# ac_switching.net
KiCad netlist of a schematic drawn in EAGLE
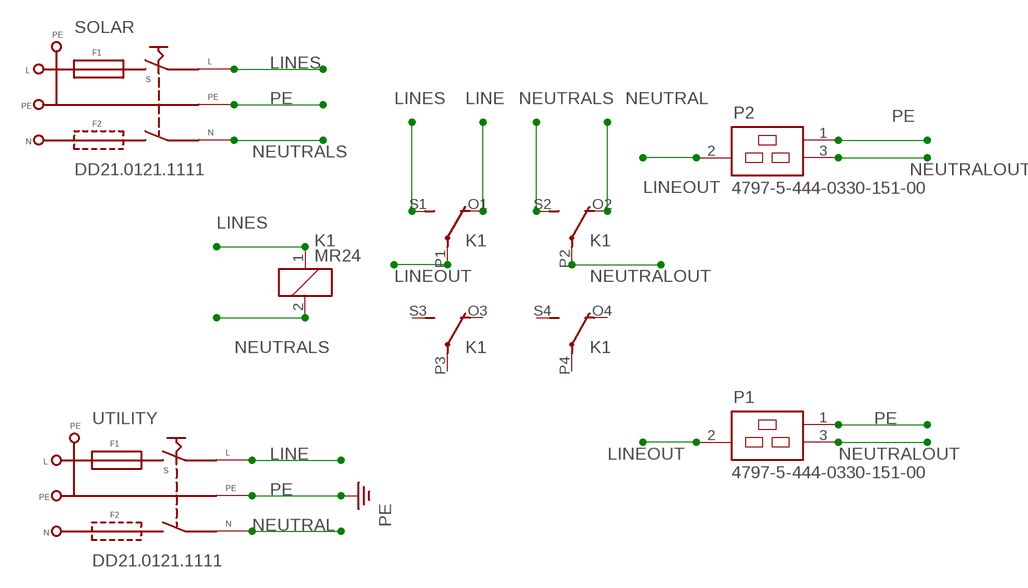
[diagram p0: schematic, sheet 1]

(export (version "E")
  (design (tool "Eeschema 10.0.6"))
  (components
    (comp (ref "K1")
      (value "MR24")
      (footprint "eagle-import:MR24")
      (libsource (lib "eagle-import") (part "MR24"))
    )
    (comp (ref "P1")
      (value "4797-5-444-0330-151-00")
      (footprint "eagle-import:SCHURTER_4797-5-444-0330-151-00")
      (fields (field (name "MF") "Schurter Inc."))
      (libsource (lib "eagle-import") (part "4797-5-444-0330-151-00"))
    )
    (comp (ref "P2")
      (value "4797-5-444-0330-151-00")
      (footprint "eagle-import:SCHURTER_4797-5-444-0330-151-00")
      (fields (field (name "MF") "Schurter Inc."))
      (libsource (lib "eagle-import") (part "4797-5-444-0330-151-00"))
    )
    (comp (ref "SOLAR")
      (value "DD21.0121.1111")
      (footprint "eagle-import:SCHURTER_DD21.0121.1111")
      (fields (field (name "MF") "Schurter Inc."))
      (libsource (lib "eagle-import") (part "DD21.0121.1111"))
    )
    (comp (ref "UTILITY")
      (value "DD21.0121.1111")
      (footprint "eagle-import:SCHURTER_DD21.0121.1111")
      (fields (field (name "MF") "Schurter Inc."))
      (libsource (lib "eagle-import") (part "DD21.0121.1111"))
    )
  )
  (nets
    (net (code "1") (name "/LINE") (class "Default")
      (node (ref "K1") (pin "O1") (pinfunction "O_O1") (pintype "passive"))
      (node (ref "UTILITY") (pin "L") (pinfunction "L_L") (pintype "power_in"))
    )
    (net (code "2") (name "/LINEOUT") (class "Default")
      (node (ref "K1") (pin "P1") (pinfunction "P_P1") (pintype "passive"))
      (node (ref "P1") (pin "2") (pinfunction "NEUTRAL_2") (pintype "power_in"))
      (node (ref "P2") (pin "2") (pinfunction "NEUTRAL_2") (pintype "power_in"))
    )
    (net (code "3") (name "/LINES") (class "Default")
      (node (ref "K1") (pin "1") (pinfunction "1_1") (pintype "passive"))
      (node (ref "K1") (pin "S1") (pinfunction "S_S1") (pintype "passive"))
      (node (ref "SOLAR") (pin "L") (pinfunction "L_L") (pintype "power_in"))
    )
    (net (code "4") (name "/NEUTRAL") (class "Default")
      (node (ref "K1") (pin "O2") (pinfunction "O_O2") (pintype "passive"))
      (node (ref "UTILITY") (pin "N") (pinfunction "N_N") (pintype "power_in"))
    )
    (net (code "5") (name "/NEUTRALOUT") (class "Default")
      (node (ref "K1") (pin "P2") (pinfunction "P_P2") (pintype "passive"))
      (node (ref "P1") (pin "3") (pinfunction "LIVE_3") (pintype "power_in"))
      (node (ref "P2") (pin "3") (pinfunction "LIVE_3") (pintype "power_in"))
    )
    (net (code "6") (name "/NEUTRALS") (class "Default")
      (node (ref "K1") (pin "2") (pinfunction "2_2") (pintype "passive"))
      (node (ref "K1") (pin "S2") (pinfunction "S_S2") (pintype "passive"))
      (node (ref "SOLAR") (pin "N") (pinfunction "N_N") (pintype "power_in"))
    )
    (net (code "7") (name "PE") (class "Default")
      (node (ref "P1") (pin "1") (pinfunction "GND_1") (pintype "power_in"))
      (node (ref "P2") (pin "1") (pinfunction "GND_1") (pintype "power_in"))
      (node (ref "SOLAR") (pin "PE") (pinfunction "PE_PE") (pintype "power_in"))
      (node (ref "UTILITY") (pin "PE") (pinfunction "PE_PE") (pintype "power_in"))
    )
    (net (code "8") (name "unconnected-(K1D-O-PadO3)") (class "Default")
      (node (ref "K1") (pin "O3") (pinfunction "O_O3") (pintype "passive"))
    )
    (net (code "9") (name "unconnected-(K1D-P-PadP3)") (class "Default")
      (node (ref "K1") (pin "P3") (pinfunction "P_P3") (pintype "passive"))
    )
    (net (code "10") (name "unconnected-(K1D-S-PadS3)") (class "Default")
      (node (ref "K1") (pin "S3") (pinfunction "S_S3") (pintype "passive"))
    )
    (net (code "11") (name "unconnected-(K1E-O-PadO4)") (class "Default")
      (node (ref "K1") (pin "O4") (pinfunction "O_O4") (pintype "passive"))
    )
    (net (code "12") (name "unconnected-(K1E-P-PadP4)") (class "Default")
      (node (ref "K1") (pin "P4") (pinfunction "P_P4") (pintype "passive"))
    )
    (net (code "13") (name "unconnected-(K1E-S-PadS4)") (class "Default")
      (node (ref "K1") (pin "S4") (pinfunction "S_S4") (pintype "passive"))
    )
  )
)
